# EtherCAT_Sheet.net
KiCad netlist of a schematic drawn in Altium Designer
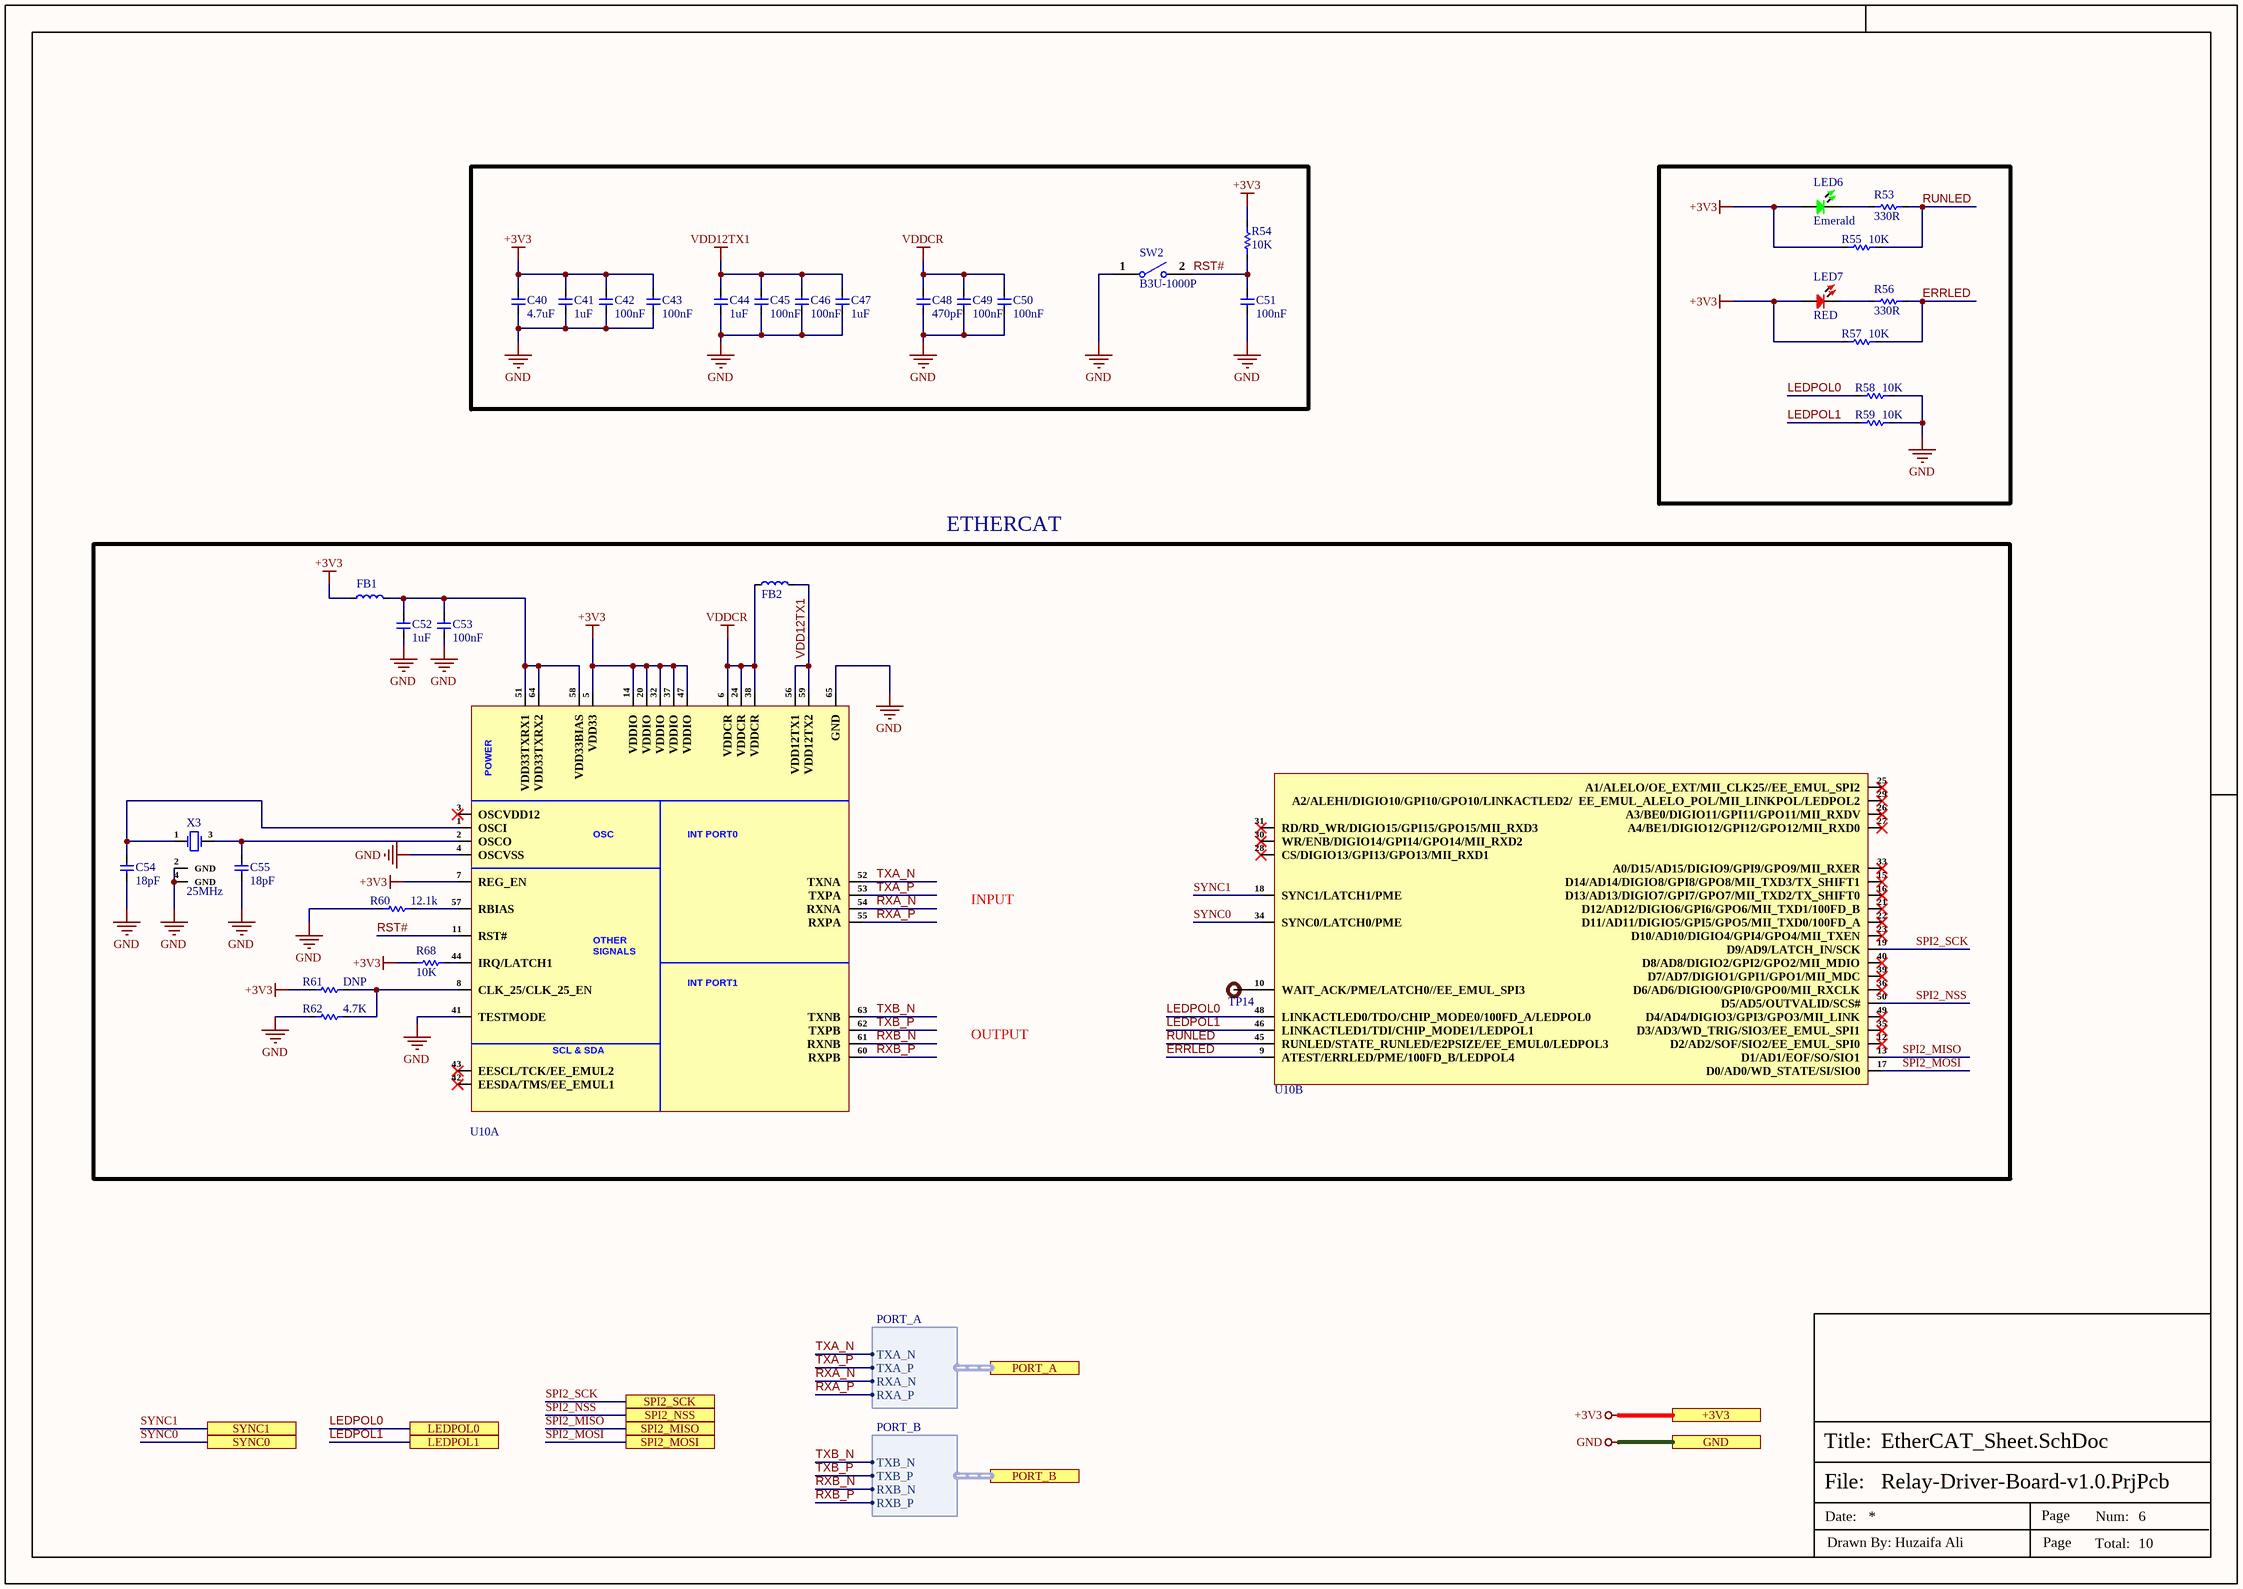
[diagram p0: EtherCAT_Sheet.SchDoc]

(export (version "E")
  (design (tool "Eeschema 10.0.6"))
  (components
    (comp (ref "C40")
      (value "4.7uF")
      (footprint "Cap-0402")
      (description "CAP CER 4.7UF 10V X5R 0402")
      (fields
        (field (name "MANUFACTURER") "Yageo")
        (field (name "MANUFACTURER PART NUMBER") "CC0402KRX5R6BB475")
      )
      (libsource (lib "eSpark Libraries") (part "CC0402KRX5R6BB475"))
    )
    (comp (ref "C41")
      (value "1uF")
      (footprint "Cap-0402")
      (description "CAP CER 1UF 10V X5R 0402")
      (fields
        (field (name "MANUFACTURER") "Yageo")
        (field (name "MANUFACTURER PART NUMBER") "CC0402KRX5R6BB105")
      )
      (libsource (lib "eSpark Libraries") (part "CC0402KRX5R6BB105"))
    )
    (comp (ref "C42")
      (value "100nF")
      (footprint "cap-0402")
      (description "CAP CER 0.1UF 50V X7R 0402")
      (fields
        (field (name "MANUFACTURER") "TDK")
        (field (name "MANUFACTURER PART NUMBER") "C1005X7R1H104KT000F")
      )
      (libsource (lib "eSpark Libraries") (part "C1005X7R1H104KT000F"))
    )
    (comp (ref "C43")
      (value "100nF")
      (footprint "cap-0402")
      (description "CAP CER 0.1UF 50V X7R 0402")
      (fields
        (field (name "MANUFACTURER") "TDK")
        (field (name "MANUFACTURER PART NUMBER") "C1005X7R1H104KT000F")
      )
      (libsource (lib "eSpark Libraries") (part "C1005X7R1H104KT000F"))
    )
    (comp (ref "C44")
      (value "1uF")
      (footprint "Cap-0402")
      (description "CAP CER 1UF 10V X5R 0402")
      (fields
        (field (name "MANUFACTURER") "Yageo")
        (field (name "MANUFACTURER PART NUMBER") "CC0402KRX5R6BB105")
      )
      (libsource (lib "eSpark Libraries") (part "CC0402KRX5R6BB105"))
    )
    (comp (ref "C45")
      (value "100nF")
      (footprint "cap-0402")
      (description "CAP CER 0.1UF 50V X7R 0402")
      (fields
        (field (name "MANUFACTURER") "TDK")
        (field (name "MANUFACTURER PART NUMBER") "C1005X7R1H104KT000F")
      )
      (libsource (lib "eSpark Libraries") (part "C1005X7R1H104KT000F"))
    )
    (comp (ref "C46")
      (value "100nF")
      (footprint "cap-0402")
      (description "CAP CER 0.1UF 50V X7R 0402")
      (fields
        (field (name "MANUFACTURER") "TDK")
        (field (name "MANUFACTURER PART NUMBER") "C1005X7R1H104KT000F")
      )
      (libsource (lib "eSpark Libraries") (part "C1005X7R1H104KT000F"))
    )
    (comp (ref "C47")
      (value "1uF")
      (footprint "Cap-0402")
      (description "CAP CER 1UF 10V X5R 0402")
      (fields
        (field (name "MANUFACTURER") "Yageo")
        (field (name "MANUFACTURER PART NUMBER") "CC0402KRX5R6BB105")
      )
      (libsource (lib "eSpark Libraries") (part "CC0402KRX5R6BB105"))
    )
    (comp (ref "C48")
      (value "470pF")
      (footprint "Cap-0603")
      (description "CAP CER 470PF 50V X7R 0603")
      (fields
        (field (name "MANUFACTURER") "Walsin Technologies")
        (field (name "MANUFACTURER PART NUMBER") "0603B471K500CT")
      )
      (libsource (lib "eSpark Libraries") (part "0603B471K500CT"))
    )
    (comp (ref "C49")
      (value "100nF")
      (footprint "cap-0402")
      (description "CAP CER 0.1UF 50V X7R 0402")
      (fields
        (field (name "MANUFACTURER") "TDK")
        (field (name "MANUFACTURER PART NUMBER") "C1005X7R1H104KT000F")
      )
      (libsource (lib "eSpark Libraries") (part "C1005X7R1H104KT000F"))
    )
    (comp (ref "C50")
      (value "100nF")
      (footprint "cap-0402")
      (description "CAP CER 0.1UF 50V X7R 0402")
      (fields
        (field (name "MANUFACTURER") "TDK")
        (field (name "MANUFACTURER PART NUMBER") "C1005X7R1H104KT000F")
      )
      (libsource (lib "eSpark Libraries") (part "C1005X7R1H104KT000F"))
    )
    (comp (ref "C51")
      (value "100nF")
      (footprint "cap-0402")
      (description "CAP CER 0.1UF 50V X7R 0402")
      (fields
        (field (name "MANUFACTURER") "TDK")
        (field (name "MANUFACTURER PART NUMBER") "C1005X7R1H104KT000F")
      )
      (libsource (lib "eSpark Libraries") (part "C1005X7R1H104KT000F"))
    )
    (comp (ref "C52")
      (value "1uF")
      (footprint "Cap-0402")
      (description "CAP CER 1UF 10V X5R 0402")
      (fields
        (field (name "MANUFACTURER") "Yageo")
        (field (name "MANUFACTURER PART NUMBER") "CC0402KRX5R6BB105")
      )
      (libsource (lib "eSpark Libraries") (part "CC0402KRX5R6BB105"))
    )
    (comp (ref "C53")
      (value "100nF")
      (footprint "cap-0402")
      (description "CAP CER 0.1UF 50V X7R 0402")
      (fields
        (field (name "MANUFACTURER") "TDK")
        (field (name "MANUFACTURER PART NUMBER") "C1005X7R1H104KT000F")
      )
      (libsource (lib "eSpark Libraries") (part "C1005X7R1H104KT000F"))
    )
    (comp (ref "C54")
      (value "18pF")
      (footprint "Cap-0402")
      (description "CAP CER 18PF 50V C0G/NP0 0402")
      (fields
        (field (name "MANUFACTURER") "Murata")
        (field (name "MANUFACTURER PART NUMBER") "GCM1555C1H180GA16D")
      )
      (libsource (lib "eSpark Libraries") (part "GCM1555C1H180GA16D"))
    )
    (comp (ref "C55")
      (value "18pF")
      (footprint "Cap-0402")
      (description "CAP CER 18PF 50V C0G/NP0 0402")
      (fields
        (field (name "MANUFACTURER") "Murata")
        (field (name "MANUFACTURER PART NUMBER") "GCM1555C1H180GA16D")
      )
      (libsource (lib "eSpark Libraries") (part "GCM1555C1H180GA16D"))
    )
    (comp (ref "FB1")
      (value "BLM15PG100SN1D")
      (footprint "IND-0402")
      (description "FERRITE BEAD 10 OHM 0402 1LN")
      (fields (field (name "MANUFACTURER") "Murata") (field (name "TOLERANCE") "25%"))
      (libsource (lib "eSpark Libraries") (part "BLM15PG100SN1D"))
    )
    (comp (ref "FB2")
      (value "BLM15PG100SN1D")
      (footprint "IND-0402")
      (description "FERRITE BEAD 10 OHM 0402 1LN")
      (fields (field (name "MANUFACTURER") "Murata") (field (name "TOLERANCE") "25%"))
      (libsource (lib "eSpark Libraries") (part "BLM15PG100SN1D"))
    )
    (comp (ref "LED6")
      (value "Emerald")
      (footprint "LED-0603")
      (description "Emerald 0603 Light Emitting Diodes (LED) ROHS")
      (fields
        (field (name "MANUFACTURER") "Foshan NationStar Optoelectronics")
        (field (name "MANUFACTURER PART NUMBER") "NCD0603G2")
      )
      (libsource (lib "eSpark Libraries") (part "NCD0603G2"))
    )
    (comp (ref "LED7")
      (value "RED")
      (footprint "LED-0603")
      (description "RED LED 0603 Light Emitting Diodes")
      (fields
        (field (name "MANUFACTURER") "Foshan NationStar Optoelectronics")
        (field (name "MANUFACTURER PART NUMBER") "NCD0603R3")
      )
      (libsource (lib "eSpark Libraries") (part "NCD0603R3"))
    )
    (comp (ref "R53")
      (value "330R")
      (footprint "Res-0603")
      (description "RES  SMD 330R 100 mW 0603")
      (fields
        (field (name "MANUFACTURER") "Yageo")
        (field (name "MANUFACTURER PART NUMBER") "RC0603JR-07330RL")
      )
      (libsource (lib "eSpark Libraries") (part "RC0603JR-07330RL"))
    )
    (comp (ref "R54")
      (value "10K")
      (footprint "Res-0402")
      (description "RES 10K OHM 1% 1/16W 0402")
      (fields
        (field (name "MANUFACTURER") "Yageo")
        (field (name "MANUFACTURER PART NUMBER") "RC0402FR-0710KL")
      )
      (libsource (lib "eSpark Libraries") (part "RC0402FR-0710KL"))
    )
    (comp (ref "R55")
      (value "10K")
      (footprint "Res-0402")
      (description "RES 10K OHM 1% 1/16W 0402")
      (fields
        (field (name "MANUFACTURER") "Yageo")
        (field (name "MANUFACTURER PART NUMBER") "RC0402FR-0710KL")
      )
      (libsource (lib "eSpark Libraries") (part "RC0402FR-0710KL"))
    )
    (comp (ref "R56")
      (value "330R")
      (footprint "Res-0603")
      (description "RES  SMD 330R 100 mW 0603")
      (fields
        (field (name "MANUFACTURER") "Yageo")
        (field (name "MANUFACTURER PART NUMBER") "RC0603JR-07330RL")
      )
      (libsource (lib "eSpark Libraries") (part "RC0603JR-07330RL"))
    )
    (comp (ref "R57")
      (value "10K")
      (footprint "Res-0402")
      (description "RES 10K OHM 1% 1/16W 0402")
      (fields
        (field (name "MANUFACTURER") "Yageo")
        (field (name "MANUFACTURER PART NUMBER") "RC0402FR-0710KL")
      )
      (libsource (lib "eSpark Libraries") (part "RC0402FR-0710KL"))
    )
    (comp (ref "R58")
      (value "10K")
      (footprint "Res-0402")
      (description "RES 10K OHM 1% 1/16W 0402")
      (fields
        (field (name "MANUFACTURER") "Yageo")
        (field (name "MANUFACTURER PART NUMBER") "RC0402FR-0710KL")
      )
      (libsource (lib "eSpark Libraries") (part "RC0402FR-0710KL"))
    )
    (comp (ref "R59")
      (value "10K")
      (footprint "Res-0402")
      (description "RES 10K OHM 1% 1/16W 0402")
      (fields
        (field (name "MANUFACTURER") "Yageo")
        (field (name "MANUFACTURER PART NUMBER") "RC0402FR-0710KL")
      )
      (libsource (lib "eSpark Libraries") (part "RC0402FR-0710KL"))
    )
    (comp (ref "R60")
      (value "12.1k")
      (footprint "Res-0402")
      (description "RES SMD 12.1KOHM 0.1% 1/16W 0402")
      (fields
        (field (name "MANUFACTURER") "Yageo")
        (field (name "MANUFACTURER PART NUMBER") "RT0402BRD0712K1L")
      )
      (libsource (lib "eSpark Libraries") (part "RT0402BRD0712K1L"))
    )
    (comp (ref "R61")
      (value "DNP")
      (footprint "Res-0402")
      (description "RES 4.7K OHM 1% 1/16W 0402")
      (fields
        (field (name "MANUFACTURER") "Yageo")
        (field (name "MANUFACTURER PART NUMBER") "RC0402FR-074K7L")
      )
      (libsource (lib "eSpark Libraries") (part "RC0402FR-074K7L"))
    )
    (comp (ref "R62")
      (value "4.7K")
      (footprint "Res-0402")
      (description "RES 4.7K OHM 1% 1/16W 0402")
      (fields
        (field (name "MANUFACTURER") "Yageo")
        (field (name "MANUFACTURER PART NUMBER") "RC0402FR-074K7L")
      )
      (libsource (lib "eSpark Libraries") (part "RC0402FR-074K7L"))
    )
    (comp (ref "R68")
      (value "10K")
      (footprint "Res-0402")
      (description "RES 10K OHM 1% 1/16W 0402")
      (fields
        (field (name "MANUFACTURER") "Yageo")
        (field (name "MANUFACTURER PART NUMBER") "RC0402FR-0710KL")
      )
      (libsource (lib "eSpark Libraries") (part "RC0402FR-0710KL"))
    )
    (comp (ref "SW2")
      (value "B3U-1000P")
      (footprint "B3U-1000P")
      (description "SWITCH TACTILE SPST-NO 0.05A 12V")
      (fields (field (name "MANUFACTURER") "Omron") (field (name "LCSC PART NUMBER") "C231329"))
      (libsource (lib "eSpark Libraries") (part "B3U-1000P"))
    )
    (comp (ref "TP14")
      (value "TEST POINT")
      (footprint "Test-point")
      (description "Test Point ON")
      (libsource (lib "eSpark Libraries") (part "TEST POINT"))
    )
    (comp (ref "U10")
      (value "LAN9253-SVB QFN64")
      (footprint "QFN-64-EP(9x9)")
      (description "2/3-PORT ETHERCAT SLAVE CTLR")
      (fields
        (field (name "MANUFACTURER") "Microchip")
        (field (name "MANUFACTURER PART NUMBER") "LAN9253-I/R4X")
      )
      (libsource (lib "eSpark Libraries") (part "LAN9253-SVB QFN64"))
    )
    (comp (ref "X3")
      (value "25MHz")
      (footprint "SMD3225-4P")
      (description "25MHz 贴片晶振 18pF ±10ppm ±20ppm SMD3225-4P Crystals ROHS")
      (fields (field (name "LCSC PART NUMBER") "C70593") (field (name "MANUFACTURER") "YXC"))
      (libsource (lib "eSpark Libraries") (part "X322525MRB4SI"))
    )
  )
  (nets
    (net (code "3") (name "+3V3") (class "Default")
      (node (ref "C40") (pin "2") (pinfunction "2_2") (pintype "passive"))
      (node (ref "C41") (pin "2") (pinfunction "2_2") (pintype "passive"))
      (node (ref "C42") (pin "2") (pinfunction "2_2") (pintype "passive"))
      (node (ref "C43") (pin "2") (pinfunction "2_2") (pintype "passive"))
      (node (ref "FB1") (pin "1") (pinfunction "1_1") (pintype "passive"))
      (node (ref "LED6") (pin "1") (pinfunction "1_1") (pintype "passive"))
      (node (ref "LED7") (pin "1") (pinfunction "1_1") (pintype "passive"))
      (node (ref "R54") (pin "1") (pinfunction "1_1") (pintype "passive"))
      (node (ref "R55") (pin "2") (pinfunction "2_2") (pintype "passive"))
      (node (ref "R57") (pin "2") (pinfunction "2_2") (pintype "passive"))
      (node (ref "R61") (pin "1") (pinfunction "1_1") (pintype "passive"))
      (node (ref "R68") (pin "1") (pinfunction "1_1") (pintype "passive"))
      (node (ref "U10") (pin "14") (pinfunction "VDDIO_14") (pintype "passive"))
      (node (ref "U10") (pin "20") (pinfunction "VDDIO_20") (pintype "passive"))
      (node (ref "U10") (pin "32") (pinfunction "VDDIO_32") (pintype "passive"))
      (node (ref "U10") (pin "37") (pinfunction "VDDIO_37") (pintype "passive"))
      (node (ref "U10") (pin "47") (pinfunction "VDDIO_47") (pintype "passive"))
      (node (ref "U10") (pin "5") (pinfunction "VDD33_5") (pintype "passive"))
      (node (ref "U10") (pin "7") (pinfunction "REG_EN_7") (pintype "passive"))
    )
    (net (code "4") (name "/ERRLED") (class "Default")
      (node (ref "R56") (pin "2") (pinfunction "2_2") (pintype "passive"))
      (node (ref "R57") (pin "1") (pinfunction "1_1") (pintype "passive"))
      (node (ref "U10") (pin "9") (pinfunction "ATEST/ERRLED/PME/100FD_B/LEDPOL4_9") (pintype "passive"))
    )
    (net (code "5") (name "/LEDPOL0") (class "Default")
      (node (ref "R58") (pin "2") (pinfunction "2_2") (pintype "passive"))
      (node (ref "U10") (pin "48") (pinfunction "LINKACTLED0/TDO/CHIP_MODE0/100FD_A/LEDPOL0_48") (pintype "passive"))
    )
    (net (code "6") (name "/LEDPOL1") (class "Default")
      (node (ref "R59") (pin "2") (pinfunction "2_2") (pintype "passive"))
      (node (ref "U10") (pin "46") (pinfunction "LINKACTLED1/TDI/CHIP_MODE1/LEDPOL1_46") (pintype "passive"))
    )
    (net (code "7") (name "/RST#") (class "Default")
      (node (ref "C51") (pin "2") (pinfunction "2_2") (pintype "passive"))
      (node (ref "R54") (pin "2") (pinfunction "2_2") (pintype "passive"))
      (node (ref "SW2") (pin "2") (pinfunction "2_2") (pintype "passive"))
      (node (ref "U10") (pin "11") (pinfunction "RST#_11") (pintype "passive"))
    )
    (net (code "8") (name "/RUNLED") (class "Default")
      (node (ref "R53") (pin "2") (pinfunction "2_2") (pintype "passive"))
      (node (ref "R55") (pin "1") (pinfunction "1_1") (pintype "passive"))
      (node (ref "U10") (pin "45") (pinfunction "RUNLED/STATE_RUNLED/E2PSIZE/EE_EMUL0/LEDPOL3_45") (pintype "passive"))
    )
    (net (code "9") (name "/RXA_N") (class "Default")
      (node (ref "U10") (pin "54") (pinfunction "RXNA_54") (pintype "passive"))
    )
    (net (code "10") (name "/RXA_P") (class "Default")
      (node (ref "U10") (pin "55") (pinfunction "RXPA_55") (pintype "passive"))
    )
    (net (code "11") (name "/RXB_N") (class "Default")
      (node (ref "U10") (pin "61") (pinfunction "RXNB_61") (pintype "passive"))
    )
    (net (code "12") (name "/RXB_P") (class "Default")
      (node (ref "U10") (pin "60") (pinfunction "RXPB_60") (pintype "passive"))
    )
    (net (code "13") (name "/SPI2_MISO") (class "Default")
      (node (ref "U10") (pin "13") (pinfunction "D1/AD1/EOF/SO/SIO1_13") (pintype "passive"))
    )
    (net (code "14") (name "/SPI2_MOSI") (class "Default")
      (node (ref "U10") (pin "17") (pinfunction "D0/AD0/WD_STATE/SI/SIO0_17") (pintype "passive"))
    )
    (net (code "15") (name "/SPI2_NSS") (class "Default")
      (node (ref "U10") (pin "50") (pinfunction "D5/AD5/OUTVALID/SCS#_50") (pintype "passive"))
    )
    (net (code "16") (name "/SPI2_SCK") (class "Default")
      (node (ref "U10") (pin "19") (pinfunction "D9/AD9/LATCH_IN/SCK_19") (pintype "passive"))
    )
    (net (code "17") (name "/SYNC0") (class "Default")
      (node (ref "U10") (pin "34") (pinfunction "SYNC0/LATCH0/PME_34") (pintype "passive"))
    )
    (net (code "18") (name "/SYNC1") (class "Default")
      (node (ref "U10") (pin "18") (pinfunction "SYNC1/LATCH1/PME_18") (pintype "passive"))
    )
    (net (code "19") (name "/TXA_N") (class "Default")
      (node (ref "U10") (pin "52") (pinfunction "TXNA_52") (pintype "passive"))
    )
    (net (code "20") (name "/TXA_P") (class "Default")
      (node (ref "U10") (pin "53") (pinfunction "TXPA_53") (pintype "passive"))
    )
    (net (code "21") (name "/TXB_N") (class "Default")
      (node (ref "U10") (pin "63") (pinfunction "TXNB_63") (pintype "passive"))
    )
    (net (code "22") (name "/TXB_P") (class "Default")
      (node (ref "U10") (pin "62") (pinfunction "TXPB_62") (pintype "passive"))
    )
    (net (code "25") (name "GND") (class "Default")
      (node (ref "C40") (pin "1") (pinfunction "1_1") (pintype "passive"))
      (node (ref "C41") (pin "1") (pinfunction "1_1") (pintype "passive"))
      (node (ref "C42") (pin "1") (pinfunction "1_1") (pintype "passive"))
      (node (ref "C43") (pin "1") (pinfunction "1_1") (pintype "passive"))
      (node (ref "C44") (pin "1") (pinfunction "1_1") (pintype "passive"))
      (node (ref "C45") (pin "1") (pinfunction "1_1") (pintype "passive"))
      (node (ref "C46") (pin "1") (pinfunction "1_1") (pintype "passive"))
      (node (ref "C47") (pin "1") (pinfunction "1_1") (pintype "passive"))
      (node (ref "C48") (pin "1") (pinfunction "1_1") (pintype "passive"))
      (node (ref "C49") (pin "1") (pinfunction "1_1") (pintype "passive"))
      (node (ref "C50") (pin "1") (pinfunction "1_1") (pintype "passive"))
      (node (ref "C51") (pin "1") (pinfunction "1_1") (pintype "passive"))
      (node (ref "C52") (pin "1") (pinfunction "1_1") (pintype "passive"))
      (node (ref "C53") (pin "1") (pinfunction "1_1") (pintype "passive"))
      (node (ref "C54") (pin "2") (pinfunction "2_2") (pintype "passive"))
      (node (ref "C55") (pin "2") (pinfunction "2_2") (pintype "passive"))
      (node (ref "R58") (pin "1") (pinfunction "1_1") (pintype "passive"))
      (node (ref "R59") (pin "1") (pinfunction "1_1") (pintype "passive"))
      (node (ref "R60") (pin "1") (pinfunction "1_1") (pintype "passive"))
      (node (ref "R62") (pin "1") (pinfunction "1_1") (pintype "passive"))
      (node (ref "SW2") (pin "1") (pinfunction "1_1") (pintype "passive"))
      (node (ref "U10") (pin "4") (pinfunction "OSCVSS_4") (pintype "passive"))
      (node (ref "U10") (pin "41") (pinfunction "TESTMODE_41") (pintype "passive"))
      (node (ref "U10") (pin "65") (pinfunction "GND_65") (pintype "passive"))
      (node (ref "X3") (pin "2") (pinfunction "GND_2") (pintype "passive"))
      (node (ref "X3") (pin "4") (pinfunction "GND_4") (pintype "passive"))
    )
    (net (code "26") (name "Net-(LED6-Pad2)") (class "Default")
      (node (ref "LED6") (pin "2") (pinfunction "2_2") (pintype "passive"))
      (node (ref "R53") (pin "1") (pinfunction "1_1") (pintype "passive"))
    )
    (net (code "27") (name "Net-(LED7-Pad2)") (class "Default")
      (node (ref "LED7") (pin "2") (pinfunction "2_2") (pintype "passive"))
      (node (ref "R56") (pin "1") (pinfunction "1_1") (pintype "passive"))
    )
    (net (code "28") (name "Net-(U10A-CLK_25{slash}CLK_25_EN)") (class "Default")
      (node (ref "R61") (pin "2") (pinfunction "2_2") (pintype "passive"))
      (node (ref "R62") (pin "2") (pinfunction "2_2") (pintype "passive"))
      (node (ref "U10") (pin "8") (pinfunction "CLK_25/CLK_25_EN_8") (pintype "passive"))
    )
    (net (code "29") (name "Net-(U10A-IRQ{slash}LATCH1)") (class "Default")
      (node (ref "R68") (pin "2") (pinfunction "2_2") (pintype "passive"))
      (node (ref "U10") (pin "44") (pinfunction "IRQ/LATCH1_44") (pintype "passive"))
    )
    (net (code "30") (name "Net-(U10A-OSCI)") (class "Default")
      (node (ref "C54") (pin "1") (pinfunction "1_1") (pintype "passive"))
      (node (ref "U10") (pin "1") (pinfunction "OSCI_1") (pintype "passive"))
      (node (ref "X3") (pin "1") (pinfunction "CRYSTAL_1") (pintype "passive"))
    )
    (net (code "31") (name "Net-(U10A-OSCO)") (class "Default")
      (node (ref "C55") (pin "1") (pinfunction "1_1") (pintype "passive"))
      (node (ref "U10") (pin "2") (pinfunction "OSCO_2") (pintype "passive"))
      (node (ref "X3") (pin "3") (pinfunction "CRYSTAL_3") (pintype "passive"))
    )
    (net (code "32") (name "Net-(U10A-RBIAS)") (class "Default")
      (node (ref "R60") (pin "2") (pinfunction "2_2") (pintype "passive"))
      (node (ref "U10") (pin "57") (pinfunction "RBIAS_57") (pintype "passive"))
    )
    (net (code "33") (name "Net-(U10A-VDD33BIAS)") (class "Default")
      (node (ref "C52") (pin "2") (pinfunction "2_2") (pintype "passive"))
      (node (ref "C53") (pin "2") (pinfunction "2_2") (pintype "passive"))
      (node (ref "FB1") (pin "2") (pinfunction "2_2") (pintype "passive"))
      (node (ref "U10") (pin "51") (pinfunction "VDD33TXRX1_51") (pintype "passive"))
      (node (ref "U10") (pin "58") (pinfunction "VDD33BIAS_58") (pintype "passive"))
      (node (ref "U10") (pin "64") (pinfunction "VDD33TXRX2_64") (pintype "passive"))
    )
    (net (code "34") (name "Net-(U10B-WAIT_ACK{slash}PME{slash}LATCH0{slash}{slash}EE_EMUL_SPI3)") (class "Default")
      (node (ref "TP14") (pin "1") (pinfunction "1_1") (pintype "passive"))
      (node (ref "U10") (pin "10") (pinfunction "WAIT_ACK/PME/LATCH0//EE_EMUL_SPI3_10") (pintype "passive"))
    )
    (net (code "35") (name "VDD12TX1") (class "Default")
      (node (ref "C44") (pin "2") (pinfunction "2_2") (pintype "passive"))
      (node (ref "C45") (pin "2") (pinfunction "2_2") (pintype "passive"))
      (node (ref "C46") (pin "2") (pinfunction "2_2") (pintype "passive"))
      (node (ref "C47") (pin "2") (pinfunction "2_2") (pintype "passive"))
      (node (ref "FB2") (pin "2") (pinfunction "2_2") (pintype "passive"))
      (node (ref "U10") (pin "56") (pinfunction "VDD12TX1_56") (pintype "passive"))
      (node (ref "U10") (pin "59") (pinfunction "VDD12TX2_59") (pintype "passive"))
    )
    (net (code "36") (name "VDDCR") (class "Default")
      (node (ref "C48") (pin "2") (pinfunction "2_2") (pintype "passive"))
      (node (ref "C49") (pin "2") (pinfunction "2_2") (pintype "passive"))
      (node (ref "C50") (pin "2") (pinfunction "2_2") (pintype "passive"))
      (node (ref "FB2") (pin "1") (pinfunction "1_1") (pintype "passive"))
      (node (ref "U10") (pin "24") (pinfunction "VDDCR_24") (pintype "passive"))
      (node (ref "U10") (pin "38") (pinfunction "VDDCR_38") (pintype "passive"))
      (node (ref "U10") (pin "6") (pinfunction "VDDCR_6") (pintype "passive"))
    )
    (net (code "37") (name "unconnected-(U10A-EESCL{slash}TCK{slash}EE_EMUL2-Pad43)") (class "Default")
      (node (ref "U10") (pin "43") (pinfunction "EESCL/TCK/EE_EMUL2_43") (pintype "passive+no_connect"))
    )
    (net (code "38") (name "unconnected-(U10A-EESDA{slash}TMS{slash}EE_EMUL1-Pad42)") (class "Default")
      (node (ref "U10") (pin "42") (pinfunction "EESDA/TMS/EE_EMUL1_42") (pintype "passive+no_connect"))
    )
    (net (code "39") (name "unconnected-(U10A-OSCVDD12-Pad3)") (class "Default")
      (node (ref "U10") (pin "3") (pinfunction "OSCVDD12_3") (pintype "passive+no_connect"))
    )
    (net (code "40") (name "unconnected-(U10B-A0{slash}D15{slash}AD15{slash}DIGIO9{slash}GPI9{slash}GPO9{slash}MII_RXER-Pad33)") (class "Default")
      (node (ref "U10") (pin "33") (pinfunction "A0/D15/AD15/DIGIO9/GPI9/GPO9/MII_RXER_33") (pintype "passive+no_connect"))
    )
    (net (code "41") (name "unconnected-(U10B-A1{slash}ALELO{slash}OE_EXT{slash}MII_CLK25{slash}{slash}EE_EMUL_SPI2-Pad25)") (class "Default")
      (node (ref "U10") (pin "25") (pinfunction "A1/ALELO/OE_EXT/MII_CLK25//EE_EMUL_SPI2_25") (pintype "passive+no_connect"))
    )
    (net (code "42") (name "unconnected-(U10B-A2{slash}ALEHI{slash}DIGIO10{slash}GPI10{slash}GPO10{slash}LINKACTLED2{slash}__EE_EMUL_ALELO_POL{slash}MII_LINKPOL{slash}LEDPOL2-Pad29)") (class "Default")
      (node (ref "U10") (pin "29") (pinfunction "A2/ALEHI/DIGIO10/GPI10/GPO10/LINKACTLED2/__EE_EMUL_ALELO_POL/MII_LINKPOL/LEDPOL2_29") (pintype "passive+no_connect"))
    )
    (net (code "43") (name "unconnected-(U10B-A3{slash}BE0{slash}DIGIO11{slash}GPI11{slash}GPO11{slash}MII_RXDV-Pad26)") (class "Default")
      (node (ref "U10") (pin "26") (pinfunction "A3/BE0/DIGIO11/GPI11/GPO11/MII_RXDV_26") (pintype "passive+no_connect"))
    )
    (net (code "44") (name "unconnected-(U10B-A4{slash}BE1{slash}DIGIO12{slash}GPI12{slash}GPO12{slash}MII_RXD0-Pad27)") (class "Default")
      (node (ref "U10") (pin "27") (pinfunction "A4/BE1/DIGIO12/GPI12/GPO12/MII_RXD0_27") (pintype "passive+no_connect"))
    )
    (net (code "45") (name "unconnected-(U10B-CS{slash}DIGIO13{slash}GPI13{slash}GPO13{slash}MII_RXD1-Pad28)") (class "Default")
      (node (ref "U10") (pin "28") (pinfunction "CS/DIGIO13/GPI13/GPO13/MII_RXD1_28") (pintype "passive+no_connect"))
    )
    (net (code "46") (name "unconnected-(U10B-D2{slash}AD2{slash}SOF{slash}SIO2{slash}EE_EMUL_SPI0-Pad12)") (class "Default")
      (node (ref "U10") (pin "12") (pinfunction "D2/AD2/SOF/SIO2/EE_EMUL_SPI0_12") (pintype "passive+no_connect"))
    )
    (net (code "47") (name "unconnected-(U10B-D3{slash}AD3{slash}WD_TRIG{slash}SIO3{slash}EE_EMUL_SPI1-Pad35)") (class "Default")
      (node (ref "U10") (pin "35") (pinfunction "D3/AD3/WD_TRIG/SIO3/EE_EMUL_SPI1_35") (pintype "passive+no_connect"))
    )
    (net (code "48") (name "unconnected-(U10B-D4{slash}AD4{slash}DIGIO3{slash}GPI3{slash}GPO3{slash}MII_LINK-Pad49)") (class "Default")
      (node (ref "U10") (pin "49") (pinfunction "D4/AD4/DIGIO3/GPI3/GPO3/MII_LINK_49") (pintype "passive+no_connect"))
    )
    (net (code "49") (name "unconnected-(U10B-D6{slash}AD6{slash}DIGIO0{slash}GPI0{slash}GPO0{slash}MII_RXCLK-Pad36)") (class "Default")
      (node (ref "U10") (pin "36") (pinfunction "D6/AD6/DIGIO0/GPI0/GPO0/MII_RXCLK_36") (pintype "passive+no_connect"))
    )
    (net (code "50") (name "unconnected-(U10B-D7{slash}AD7{slash}DIGIO1{slash}GPI1{slash}GPO1{slash}MII_MDC-Pad39)") (class "Default")
      (node (ref "U10") (pin "39") (pinfunction "D7/AD7/DIGIO1/GPI1/GPO1/MII_MDC_39") (pintype "passive+no_connect"))
    )
    (net (code "51") (name "unconnected-(U10B-D8{slash}AD8{slash}DIGIO2{slash}GPI2{slash}GPO2{slash}MII_MDIO-Pad40)") (class "Default")
      (node (ref "U10") (pin "40") (pinfunction "D8/AD8/DIGIO2/GPI2/GPO2/MII_MDIO_40") (pintype "passive+no_connect"))
    )
    (net (code "52") (name "unconnected-(U10B-D10{slash}AD10{slash}DIGIO4{slash}GPI4{slash}GPO4{slash}MII_TXEN-Pad23)") (class "Default")
      (node (ref "U10") (pin "23") (pinfunction "D10/AD10/DIGIO4/GPI4/GPO4/MII_TXEN_23") (pintype "passive+no_connect"))
    )
    (net (code "53") (name "unconnected-(U10B-D11{slash}AD11{slash}DIGIO5{slash}GPI5{slash}GPO5{slash}MII_TXD0{slash}100FD_A-Pad22)") (class "Default")
      (node (ref "U10") (pin "22") (pinfunction "D11/AD11/DIGIO5/GPI5/GPO5/MII_TXD0/100FD_A_22") (pintype "passive+no_connect"))
    )
    (net (code "54") (name "unconnected-(U10B-D12{slash}AD12{slash}DIGIO6{slash}GPI6{slash}GPO6{slash}MII_TXD1{slash}100FD_B-Pad21)") (class "Default")
      (node (ref "U10") (pin "21") (pinfunction "D12/AD12/DIGIO6/GPI6/GPO6/MII_TXD1/100FD_B_21") (pintype "passive+no_connect"))
    )
    (net (code "55") (name "unconnected-(U10B-D13{slash}AD13{slash}DIGIO7{slash}GPI7{slash}GPO7{slash}MII_TXD2{slash}TX_SHIFT0-Pad16)") (class "Default")
      (node (ref "U10") (pin "16") (pinfunction "D13/AD13/DIGIO7/GPI7/GPO7/MII_TXD2/TX_SHIFT0_16") (pintype "passive+no_connect"))
    )
    (net (code "56") (name "unconnected-(U10B-D14{slash}AD14{slash}DIGIO8{slash}GPI8{slash}GPO8{slash}MII_TXD3{slash}TX_SHIFT1-Pad15)") (class "Default")
      (node (ref "U10") (pin "15") (pinfunction "D14/AD14/DIGIO8/GPI8/GPO8/MII_TXD3/TX_SHIFT1_15") (pintype "passive+no_connect"))
    )
    (net (code "57") (name "unconnected-(U10B-RD{slash}RD_WR{slash}DIGIO15{slash}GPI15{slash}GPO15{slash}MII_RXD3-Pad31)") (class "Default")
      (node (ref "U10") (pin "31") (pinfunction "RD/RD_WR/DIGIO15/GPI15/GPO15/MII_RXD3_31") (pintype "passive+no_connect"))
    )
    (net (code "58") (name "unconnected-(U10B-WR{slash}ENB{slash}DIGIO14{slash}GPI14{slash}GPO14{slash}MII_RXD2-Pad30)") (class "Default")
      (node (ref "U10") (pin "30") (pinfunction "WR/ENB/DIGIO14/GPI14/GPO14/MII_RXD2_30") (pintype "passive+no_connect"))
    )
  )
)
